# RFControlBoard.net
KiCad netlist of a schematic drawn in EAGLE
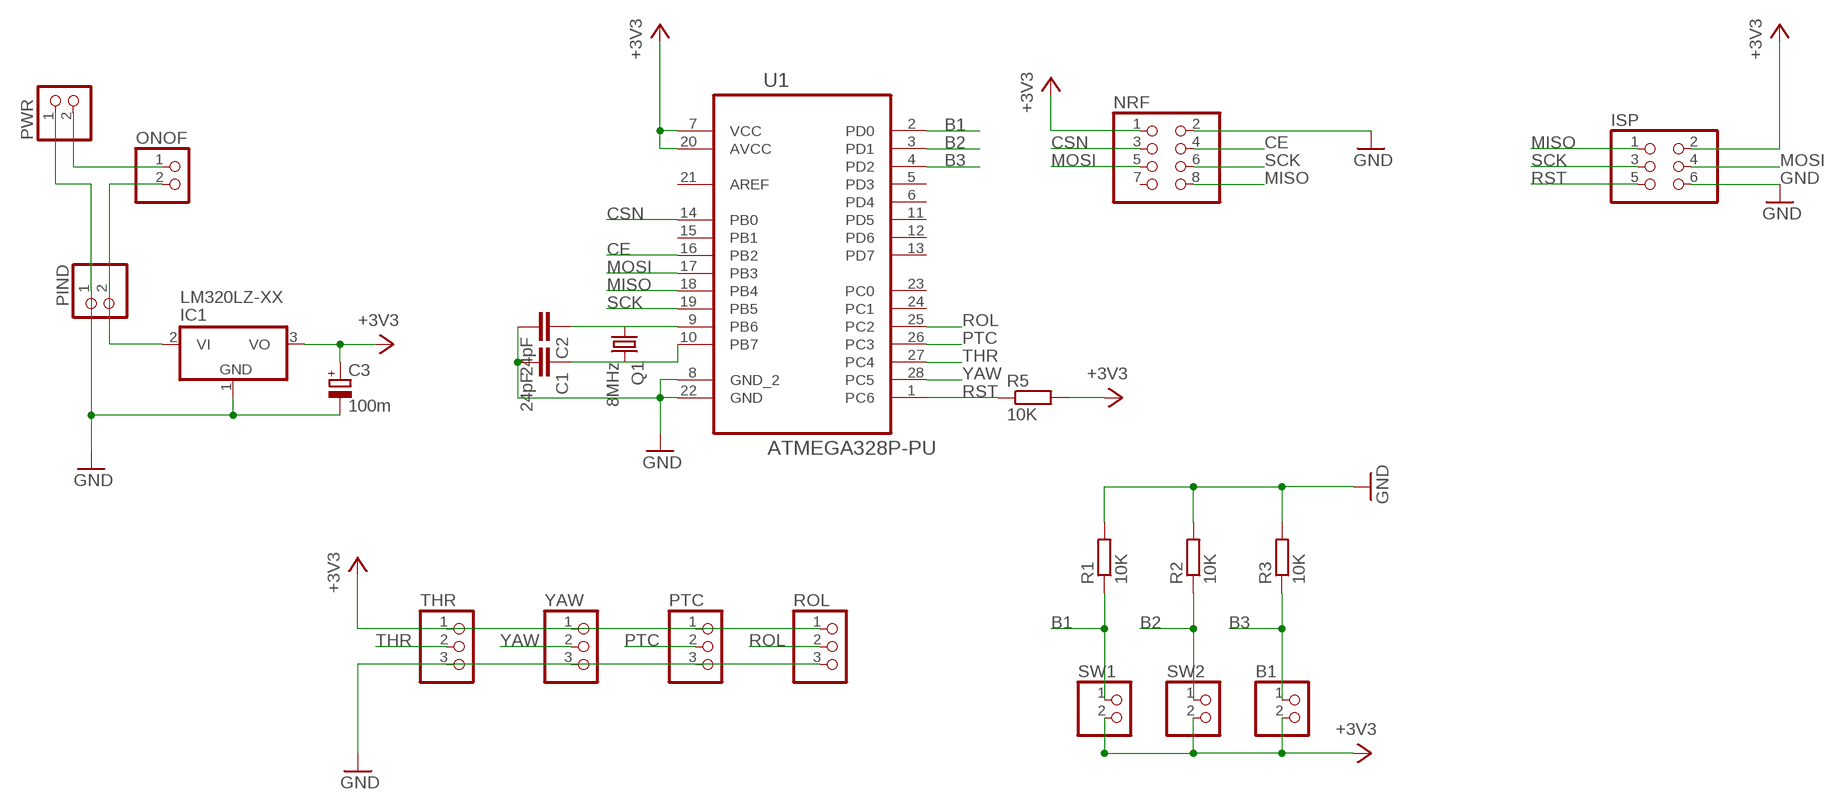
[diagram p0: schematic, sheet 1]

(export (version "E")
  (design (tool "Eeschema 10.0.6"))
  (components
    (comp (ref "B1")
      (value "PINHD-1X2")
      (footprint "eagle-import:1X02")
      (libsource (lib "eagle-import") (part "PINHD-1X2"))
    )
    (comp (ref "C1")
      (value "24pF")
      (footprint "eagle-import:C2.5-3")
      (libsource (lib "eagle-import") (part "C2,5-3"))
    )
    (comp (ref "C2")
      (value "24pF")
      (footprint "eagle-import:C2.5-3")
      (libsource (lib "eagle-import") (part "C2,5-3"))
    )
    (comp (ref "C3")
      (value "100m")
      (footprint "eagle-import:E2,5-6")
      (libsource (lib "eagle-import") (part "CPOL-EUE2.5-6"))
    )
    (comp (ref "IC1")
      (value "LM320LZ-XX")
      (footprint "eagle-import:TO92")
      (libsource (lib "eagle-import") (part "LM320LZ-XX"))
    )
    (comp (ref "ISP")
      (value "PINHD-2X3")
      (footprint "eagle-import:2X03")
      (libsource (lib "eagle-import") (part "PINHD-2X3"))
    )
    (comp (ref "NRF")
      (value "PINHD-2X4")
      (footprint "eagle-import:2X04")
      (libsource (lib "eagle-import") (part "PINHD-2X4"))
    )
    (comp (ref "ONOF")
      (value "PINHD-1X2")
      (footprint "eagle-import:1X02")
      (libsource (lib "eagle-import") (part "PINHD-1X2"))
    )
    (comp (ref "PIND")
      (value "PINHD-1X2")
      (footprint "eagle-import:1X02")
      (libsource (lib "eagle-import") (part "PINHD-1X2"))
    )
    (comp (ref "PTC")
      (value "PINHD-1X3")
      (footprint "eagle-import:1X03")
      (libsource (lib "eagle-import") (part "PINHD-1X3"))
    )
    (comp (ref "PWR")
      (value "PINHD-1X2")
      (footprint "eagle-import:1X02")
      (libsource (lib "eagle-import") (part "PINHD-1X2"))
    )
    (comp (ref "Q1")
      (value "8MHz")
      (footprint "eagle-import:HC49_S")
      (libsource (lib "eagle-import") (part "CRYSTALHC49S"))
    )
    (comp (ref "R1")
      (value "10K")
      (footprint "eagle-import:0207_10")
      (libsource (lib "eagle-import") (part "R-EU_0207/10"))
    )
    (comp (ref "R2")
      (value "10K")
      (footprint "eagle-import:0207_10")
      (libsource (lib "eagle-import") (part "R-EU_0207/10"))
    )
    (comp (ref "R3")
      (value "10K")
      (footprint "eagle-import:0207_10")
      (libsource (lib "eagle-import") (part "R-EU_0207/10"))
    )
    (comp (ref "R5")
      (value "10K")
      (footprint "eagle-import:0207_15")
      (libsource (lib "eagle-import") (part "R-EU_0207/15"))
    )
    (comp (ref "ROL")
      (value "PINHD-1X3")
      (footprint "eagle-import:1X03")
      (libsource (lib "eagle-import") (part "PINHD-1X3"))
    )
    (comp (ref "SW1")
      (value "PINHD-1X2")
      (footprint "eagle-import:1X02")
      (libsource (lib "eagle-import") (part "PINHD-1X2"))
    )
    (comp (ref "SW2")
      (value "PINHD-1X2")
      (footprint "eagle-import:1X02")
      (libsource (lib "eagle-import") (part "PINHD-1X2"))
    )
    (comp (ref "THR")
      (value "PINHD-1X3")
      (footprint "eagle-import:1X03")
      (libsource (lib "eagle-import") (part "PINHD-1X3"))
    )
    (comp (ref "U1")
      (value "ATMEGA328P-PU")
      (footprint "eagle-import:DIP254P762X457-28")
      (libsource (lib "eagle-import") (part "ATMEGA328P-PU"))
    )
    (comp (ref "YAW")
      (value "PINHD-1X3")
      (footprint "eagle-import:1X03")
      (libsource (lib "eagle-import") (part "PINHD-1X3"))
    )
  )
  (nets
    (net (code "1") (name "+3V3") (class "Default")
      (node (ref "B1") (pin "2") (pinfunction "2_2") (pintype "passive"))
      (node (ref "C3") (pin "+") (pinfunction "+_+") (pintype "passive"))
      (node (ref "IC1") (pin "3") (pinfunction "VO_3") (pintype "passive"))
      (node (ref "ISP") (pin "2") (pinfunction "2_2") (pintype "passive"))
      (node (ref "NRF") (pin "1") (pinfunction "1_1") (pintype "passive"))
      (node (ref "PTC") (pin "1") (pinfunction "1_1") (pintype "passive"))
      (node (ref "R5") (pin "2") (pinfunction "2_2") (pintype "passive"))
      (node (ref "ROL") (pin "1") (pinfunction "1_1") (pintype "passive"))
      (node (ref "SW1") (pin "2") (pinfunction "2_2") (pintype "passive"))
      (node (ref "SW2") (pin "2") (pinfunction "2_2") (pintype "passive"))
      (node (ref "THR") (pin "1") (pinfunction "1_1") (pintype "passive"))
      (node (ref "U1") (pin "20") (pinfunction "AVCC_20") (pintype "power_in"))
      (node (ref "U1") (pin "7") (pinfunction "VCC_7") (pintype "power_in"))
      (node (ref "YAW") (pin "1") (pinfunction "1_1") (pintype "passive"))
    )
    (net (code "2") (name "/B1") (class "Default")
      (node (ref "R1") (pin "1") (pinfunction "1_1") (pintype "passive"))
      (node (ref "SW1") (pin "1") (pinfunction "1_1") (pintype "passive"))
      (node (ref "U1") (pin "2") (pinfunction "PD0_2") (pintype "bidirectional"))
    )
    (net (code "3") (name "/B2") (class "Default")
      (node (ref "R2") (pin "1") (pinfunction "1_1") (pintype "passive"))
      (node (ref "SW2") (pin "1") (pinfunction "1_1") (pintype "passive"))
      (node (ref "U1") (pin "3") (pinfunction "PD1_3") (pintype "bidirectional"))
    )
    (net (code "4") (name "/B3") (class "Default")
      (node (ref "B1") (pin "1") (pinfunction "1_1") (pintype "passive"))
      (node (ref "R3") (pin "1") (pinfunction "1_1") (pintype "passive"))
      (node (ref "U1") (pin "4") (pinfunction "PD2_4") (pintype "bidirectional"))
    )
    (net (code "5") (name "/CE") (class "Default")
      (node (ref "NRF") (pin "4") (pinfunction "4_4") (pintype "passive"))
      (node (ref "U1") (pin "16") (pinfunction "PB2_16") (pintype "bidirectional"))
    )
    (net (code "6") (name "/CSN") (class "Default")
      (node (ref "NRF") (pin "3") (pinfunction "3_3") (pintype "passive"))
      (node (ref "U1") (pin "14") (pinfunction "PB0_14") (pintype "bidirectional"))
    )
    (net (code "7") (name "/MISO") (class "Default")
      (node (ref "ISP") (pin "1") (pinfunction "1_1") (pintype "passive"))
      (node (ref "NRF") (pin "8") (pinfunction "8_8") (pintype "passive"))
      (node (ref "U1") (pin "18") (pinfunction "PB4_18") (pintype "bidirectional"))
    )
    (net (code "8") (name "/MOSI") (class "Default")
      (node (ref "ISP") (pin "4") (pinfunction "4_4") (pintype "passive"))
      (node (ref "NRF") (pin "5") (pinfunction "5_5") (pintype "passive"))
      (node (ref "U1") (pin "17") (pinfunction "PB3_17") (pintype "bidirectional"))
    )
    (net (code "9") (name "/PTC") (class "Default")
      (node (ref "PTC") (pin "2") (pinfunction "2_2") (pintype "passive"))
      (node (ref "U1") (pin "26") (pinfunction "PC3_26") (pintype "bidirectional"))
    )
    (net (code "10") (name "/ROL") (class "Default")
      (node (ref "ROL") (pin "2") (pinfunction "2_2") (pintype "passive"))
      (node (ref "U1") (pin "25") (pinfunction "PC2_25") (pintype "bidirectional"))
    )
    (net (code "11") (name "/RST") (class "Default")
      (node (ref "ISP") (pin "5") (pinfunction "5_5") (pintype "passive"))
      (node (ref "R5") (pin "1") (pinfunction "1_1") (pintype "passive"))
      (node (ref "U1") (pin "1") (pinfunction "PC6_1") (pintype "bidirectional"))
    )
    (net (code "12") (name "/SCK") (class "Default")
      (node (ref "ISP") (pin "3") (pinfunction "3_3") (pintype "passive"))
      (node (ref "NRF") (pin "6") (pinfunction "6_6") (pintype "passive"))
      (node (ref "U1") (pin "19") (pinfunction "PB5_19") (pintype "bidirectional"))
    )
    (net (code "13") (name "/THR") (class "Default")
      (node (ref "THR") (pin "2") (pinfunction "2_2") (pintype "passive"))
      (node (ref "U1") (pin "27") (pinfunction "PC4_27") (pintype "bidirectional"))
    )
    (net (code "14") (name "/YAW") (class "Default")
      (node (ref "U1") (pin "28") (pinfunction "PC5_28") (pintype "bidirectional"))
      (node (ref "YAW") (pin "2") (pinfunction "2_2") (pintype "passive"))
    )
    (net (code "15") (name "GND") (class "Default")
      (node (ref "C1") (pin "2") (pinfunction "2_2") (pintype "passive"))
      (node (ref "C2") (pin "2") (pinfunction "2_2") (pintype "passive"))
      (node (ref "C3") (pin "-") (pinfunction "-_-") (pintype "passive"))
      (node (ref "IC1") (pin "1") (pinfunction "GND_1") (pintype "passive"))
      (node (ref "ISP") (pin "6") (pinfunction "6_6") (pintype "passive"))
      (node (ref "NRF") (pin "2") (pinfunction "2_2") (pintype "passive"))
      (node (ref "PIND") (pin "1") (pinfunction "1_1") (pintype "passive"))
      (node (ref "PTC") (pin "3") (pinfunction "3_3") (pintype "passive"))
      (node (ref "PWR") (pin "1") (pinfunction "1_1") (pintype "passive"))
      (node (ref "R1") (pin "2") (pinfunction "2_2") (pintype "passive"))
      (node (ref "R2") (pin "2") (pinfunction "2_2") (pintype "passive"))
      (node (ref "R3") (pin "2") (pinfunction "2_2") (pintype "passive"))
      (node (ref "ROL") (pin "3") (pinfunction "3_3") (pintype "passive"))
      (node (ref "THR") (pin "3") (pinfunction "3_3") (pintype "passive"))
      (node (ref "U1") (pin "22") (pinfunction "GND_22") (pintype "passive"))
      (node (ref "U1") (pin "8") (pinfunction "GND_2_8") (pintype "passive"))
      (node (ref "YAW") (pin "3") (pinfunction "3_3") (pintype "passive"))
    )
    (net (code "16") (name "Net-(IC1-VI)") (class "Default")
      (node (ref "IC1") (pin "2") (pinfunction "VI_2") (pintype "input"))
      (node (ref "ONOF") (pin "2") (pinfunction "2_2") (pintype "passive"))
      (node (ref "PIND") (pin "2") (pinfunction "2_2") (pintype "passive"))
    )
    (net (code "17") (name "Net-(ONOF-Pad1)") (class "Default")
      (node (ref "ONOF") (pin "1") (pinfunction "1_1") (pintype "passive"))
      (node (ref "PWR") (pin "2") (pinfunction "2_2") (pintype "passive"))
    )
    (net (code "18") (name "Net-(U1-PB6)") (class "Default")
      (node (ref "C2") (pin "1") (pinfunction "1_1") (pintype "passive"))
      (node (ref "Q1") (pin "1") (pinfunction "1_1") (pintype "passive"))
      (node (ref "U1") (pin "9") (pinfunction "PB6_9") (pintype "bidirectional"))
    )
    (net (code "19") (name "Net-(U1-PB7)") (class "Default")
      (node (ref "C1") (pin "1") (pinfunction "1_1") (pintype "passive"))
      (node (ref "Q1") (pin "2") (pinfunction "2_2") (pintype "passive"))
      (node (ref "U1") (pin "10") (pinfunction "PB7_10") (pintype "bidirectional"))
    )
    (net (code "20") (name "unconnected-(NRF-Pad7)") (class "Default")
      (node (ref "NRF") (pin "7") (pinfunction "7_7") (pintype "passive"))
    )
    (net (code "21") (name "unconnected-(U1-AREF-Pad21)") (class "Default")
      (node (ref "U1") (pin "21") (pinfunction "AREF_21") (pintype "input"))
    )
    (net (code "22") (name "unconnected-(U1-PB1-Pad15)") (class "Default")
      (node (ref "U1") (pin "15") (pinfunction "PB1_15") (pintype "bidirectional"))
    )
    (net (code "23") (name "unconnected-(U1-PC0-Pad23)") (class "Default")
      (node (ref "U1") (pin "23") (pinfunction "PC0_23") (pintype "bidirectional"))
    )
    (net (code "24") (name "unconnected-(U1-PC1-Pad24)") (class "Default")
      (node (ref "U1") (pin "24") (pinfunction "PC1_24") (pintype "bidirectional"))
    )
    (net (code "25") (name "unconnected-(U1-PD3-Pad5)") (class "Default")
      (node (ref "U1") (pin "5") (pinfunction "PD3_5") (pintype "bidirectional"))
    )
    (net (code "26") (name "unconnected-(U1-PD4-Pad6)") (class "Default")
      (node (ref "U1") (pin "6") (pinfunction "PD4_6") (pintype "bidirectional"))
    )
    (net (code "27") (name "unconnected-(U1-PD5-Pad11)") (class "Default")
      (node (ref "U1") (pin "11") (pinfunction "PD5_11") (pintype "bidirectional"))
    )
    (net (code "28") (name "unconnected-(U1-PD6-Pad12)") (class "Default")
      (node (ref "U1") (pin "12") (pinfunction "PD6_12") (pintype "bidirectional"))
    )
    (net (code "29") (name "unconnected-(U1-PD7-Pad13)") (class "Default")
      (node (ref "U1") (pin "13") (pinfunction "PD7_13") (pintype "bidirectional"))
    )
  )
)
